# lpc812bed.net
KiCad netlist of a schematic drawn in EAGLE
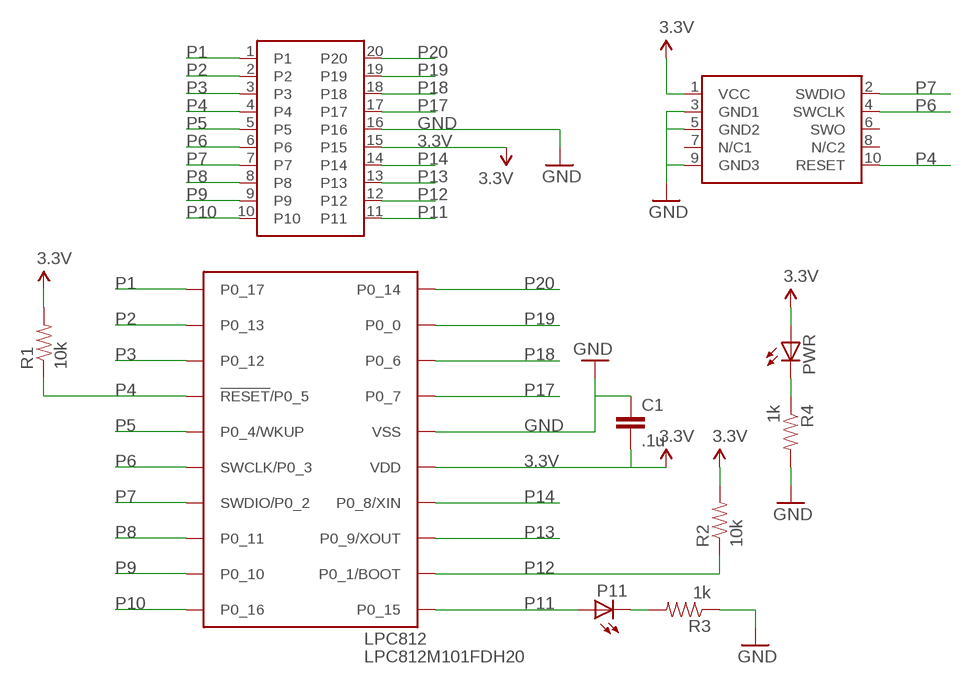
[diagram p0: schematic, sheet 1]

(export (version "E")
  (design (tool "Eeschema 10.0.6"))
  (components
    (comp (ref "C1")
      (value ".1u")
      (footprint "eagle-import:0805")
      (libsource (lib "eagle-import") (part "CAP0805"))
    )
    (comp (ref "LPC812")
      (value "LPC812M101FDH20")
      (footprint "eagle-import:TSSOP20")
      (libsource (lib "eagle-import") (part "LPC812M101FDH20"))
    )
    (comp (ref "P11")
      (value "LED1206")
      (footprint "eagle-import:LED-1206")
      (libsource (lib "eagle-import") (part "LED1206"))
    )
    (comp (ref "PWR")
      (value "LED1206")
      (footprint "eagle-import:LED-1206")
      (libsource (lib "eagle-import") (part "LED1206"))
    )
    (comp (ref "R1")
      (value "10k")
      (footprint "eagle-import:1206")
      (libsource (lib "eagle-import") (part "RESISTOR1206"))
    )
    (comp (ref "R2")
      (value "10k")
      (footprint "eagle-import:1206")
      (libsource (lib "eagle-import") (part "RESISTOR1206"))
    )
    (comp (ref "R3")
      (value "1k")
      (footprint "eagle-import:1206")
      (libsource (lib "eagle-import") (part "RESISTOR1206"))
    )
    (comp (ref "R4")
      (value "1k")
      (footprint "eagle-import:1206")
      (libsource (lib "eagle-import") (part "RESISTOR1206"))
    )
    (comp (ref "SWD1")
      (value "CORTEX_SWD")
      (footprint "eagle-import:M50-3600542")
      (libsource (lib "eagle-import") (part "CORTEX_SWD"))
    )
    (comp (ref "U$2")
      (value "LPCBOARD")
      (footprint "eagle-import:LPCBOARD_SPACERS")
      (libsource (lib "eagle-import") (part "LPCBOARD"))
    )
  )
  (nets
    (net (code "1") (name "/P1") (class "Default")
      (node (ref "LPC812") (pin "1") (pinfunction "P0_17_1") (pintype "bidirectional"))
      (node (ref "U$2") (pin "1") (pinfunction "P1_1") (pintype "bidirectional"))
    )
    (net (code "2") (name "/P2") (class "Default")
      (node (ref "LPC812") (pin "2") (pinfunction "P0_13_2") (pintype "bidirectional"))
      (node (ref "U$2") (pin "2") (pinfunction "P2_2") (pintype "bidirectional"))
    )
    (net (code "3") (name "/P3") (class "Default")
      (node (ref "LPC812") (pin "3") (pinfunction "P0_12_3") (pintype "bidirectional"))
      (node (ref "U$2") (pin "3") (pinfunction "P3_3") (pintype "bidirectional"))
    )
    (net (code "4") (name "/P4") (class "Default")
      (node (ref "LPC812") (pin "4") (pinfunction "~{RESET}/P0_5_4") (pintype "bidirectional"))
      (node (ref "R1") (pin "1") (pinfunction "1_1") (pintype "passive"))
      (node (ref "SWD1") (pin "10") (pinfunction "RESET_10") (pintype "bidirectional"))
      (node (ref "U$2") (pin "4") (pinfunction "P4_4") (pintype "bidirectional"))
    )
    (net (code "5") (name "/P5") (class "Default")
      (node (ref "LPC812") (pin "5") (pinfunction "P0_4/WKUP_5") (pintype "bidirectional"))
      (node (ref "U$2") (pin "5") (pinfunction "P5_5") (pintype "bidirectional"))
    )
    (net (code "6") (name "/P6") (class "Default")
      (node (ref "LPC812") (pin "6") (pinfunction "SWCLK/P0_3_6") (pintype "bidirectional"))
      (node (ref "SWD1") (pin "4") (pinfunction "SWCLK_4") (pintype "bidirectional"))
      (node (ref "U$2") (pin "6") (pinfunction "P6_6") (pintype "bidirectional"))
    )
    (net (code "7") (name "/P7") (class "Default")
      (node (ref "LPC812") (pin "7") (pinfunction "SWDIO/P0_2_7") (pintype "bidirectional"))
      (node (ref "SWD1") (pin "2") (pinfunction "SWDIO_2") (pintype "bidirectional"))
      (node (ref "U$2") (pin "7") (pinfunction "P7_7") (pintype "bidirectional"))
    )
    (net (code "8") (name "/P8") (class "Default")
      (node (ref "LPC812") (pin "8") (pinfunction "P0_11_8") (pintype "bidirectional"))
      (node (ref "U$2") (pin "8") (pinfunction "P8_8") (pintype "bidirectional"))
    )
    (net (code "9") (name "/P9") (class "Default")
      (node (ref "LPC812") (pin "9") (pinfunction "P0_10_9") (pintype "bidirectional"))
      (node (ref "U$2") (pin "9") (pinfunction "P9_9") (pintype "bidirectional"))
    )
    (net (code "10") (name "/P10") (class "Default")
      (node (ref "LPC812") (pin "10") (pinfunction "P0_16_10") (pintype "bidirectional"))
      (node (ref "U$2") (pin "10") (pinfunction "P10_10") (pintype "bidirectional"))
    )
    (net (code "11") (name "/P11") (class "Default")
      (node (ref "LPC812") (pin "11") (pinfunction "P0_15_11") (pintype "bidirectional"))
      (node (ref "P11") (pin "A") (pinfunction "A_A") (pintype "passive"))
      (node (ref "U$2") (pin "11") (pinfunction "P11_11") (pintype "bidirectional"))
    )
    (net (code "12") (name "/P12") (class "Default")
      (node (ref "LPC812") (pin "12") (pinfunction "P0_1/BOOT_12") (pintype "bidirectional"))
      (node (ref "R2") (pin "1") (pinfunction "1_1") (pintype "passive"))
      (node (ref "U$2") (pin "12") (pinfunction "P12_12") (pintype "bidirectional"))
    )
    (net (code "13") (name "/P13") (class "Default")
      (node (ref "LPC812") (pin "13") (pinfunction "P0_9/XOUT_13") (pintype "bidirectional"))
      (node (ref "U$2") (pin "13") (pinfunction "P13_13") (pintype "bidirectional"))
    )
    (net (code "14") (name "/P14") (class "Default")
      (node (ref "LPC812") (pin "14") (pinfunction "P0_8/XIN_14") (pintype "bidirectional"))
      (node (ref "U$2") (pin "14") (pinfunction "P14_14") (pintype "bidirectional"))
    )
    (net (code "15") (name "/P17") (class "Default")
      (node (ref "LPC812") (pin "17") (pinfunction "P0_7_17") (pintype "bidirectional"))
      (node (ref "U$2") (pin "17") (pinfunction "P17_17") (pintype "bidirectional"))
    )
    (net (code "16") (name "/P18") (class "Default")
      (node (ref "LPC812") (pin "18") (pinfunction "P0_6_18") (pintype "bidirectional"))
      (node (ref "U$2") (pin "18") (pinfunction "P18_18") (pintype "bidirectional"))
    )
    (net (code "17") (name "/P19") (class "Default")
      (node (ref "LPC812") (pin "19") (pinfunction "P0_0_19") (pintype "bidirectional"))
      (node (ref "U$2") (pin "19") (pinfunction "P19_19") (pintype "bidirectional"))
    )
    (net (code "18") (name "/P20") (class "Default")
      (node (ref "LPC812") (pin "20") (pinfunction "P0_14_20") (pintype "bidirectional"))
      (node (ref "U$2") (pin "20") (pinfunction "P20_20") (pintype "bidirectional"))
    )
    (net (code "19") (name "3.3V") (class "Default")
      (node (ref "C1") (pin "2") (pinfunction "2_2") (pintype "passive"))
      (node (ref "LPC812") (pin "15") (pinfunction "VDD_15") (pintype "bidirectional"))
      (node (ref "PWR") (pin "A") (pinfunction "A_A") (pintype "passive"))
      (node (ref "R1") (pin "2") (pinfunction "2_2") (pintype "passive"))
      (node (ref "R2") (pin "2") (pinfunction "2_2") (pintype "passive"))
      (node (ref "SWD1") (pin "1") (pinfunction "VCC_1") (pintype "bidirectional"))
      (node (ref "U$2") (pin "15") (pinfunction "P15_15") (pintype "bidirectional"))
    )
    (net (code "20") (name "GND") (class "Default")
      (node (ref "C1") (pin "1") (pinfunction "1_1") (pintype "passive"))
      (node (ref "LPC812") (pin "16") (pinfunction "VSS_16") (pintype "bidirectional"))
      (node (ref "R3") (pin "1") (pinfunction "1_1") (pintype "passive"))
      (node (ref "R4") (pin "2") (pinfunction "2_2") (pintype "passive"))
      (node (ref "SWD1") (pin "3") (pinfunction "GND1_3") (pintype "bidirectional"))
      (node (ref "SWD1") (pin "5") (pinfunction "GND2_5") (pintype "bidirectional"))
      (node (ref "SWD1") (pin "9") (pinfunction "GND3_9") (pintype "bidirectional"))
      (node (ref "U$2") (pin "16") (pinfunction "P16_16") (pintype "bidirectional"))
    )
    (net (code "21") (name "Net-(P11-PadC)") (class "Default")
      (node (ref "P11") (pin "C") (pinfunction "C_C") (pintype "passive"))
      (node (ref "R3") (pin "2") (pinfunction "2_2") (pintype "passive"))
    )
    (net (code "22") (name "Net-(PWR-PadC)") (class "Default")
      (node (ref "PWR") (pin "C") (pinfunction "C_C") (pintype "passive"))
      (node (ref "R4") (pin "1") (pinfunction "1_1") (pintype "passive"))
    )
    (net (code "23") (name "unconnected-(SWD1-N{slash}C1-Pad7)") (class "Default")
      (node (ref "SWD1") (pin "7") (pinfunction "N/C1_7") (pintype "bidirectional"))
    )
    (net (code "24") (name "unconnected-(SWD1-N{slash}C2-Pad8)") (class "Default")
      (node (ref "SWD1") (pin "8") (pinfunction "N/C2_8") (pintype "bidirectional"))
    )
    (net (code "25") (name "unconnected-(SWD1-SWO-Pad6)") (class "Default")
      (node (ref "SWD1") (pin "6") (pinfunction "SWO_6") (pintype "bidirectional"))
    )
  )
)
